# ATRACK_KEY_V1.net
KiCad netlist of a schematic drawn in Altium Designer
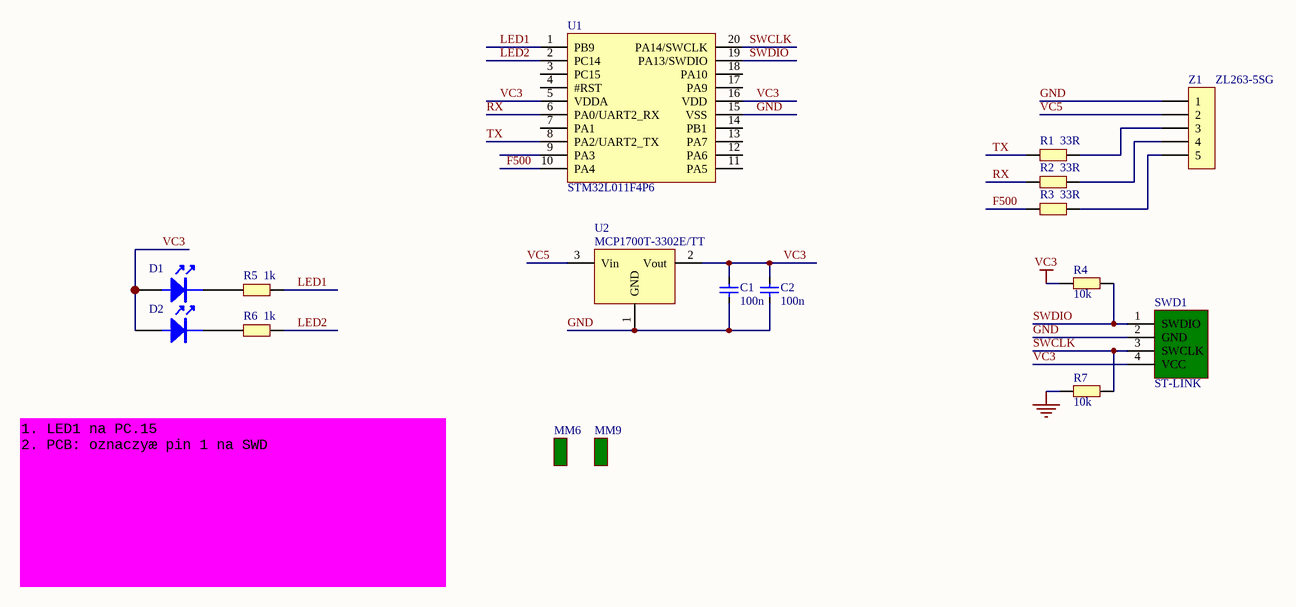
[diagram p0: ATRACK_KEY_V1.SchDoc]

(export (version "E")
  (design (tool "Eeschema 10.0.6"))
  (components
    (comp (ref "C1") (value "100n") (footprint "0603C") (libsource (lib "*") (part "CAP")))
    (comp (ref "C2") (value "100n") (footprint "0603C") (libsource (lib "*") (part "CAP")))
    (comp (ref "D1") (value "~") (footprint "0603LG") (libsource (lib "*") (part "LED")))
    (comp (ref "D2") (value "~") (footprint "0603LR") (libsource (lib "*") (part "LED")))
    (comp (ref "MM6") (value "~") (footprint "REF_CIR") (libsource (lib "*") (part "MECH")))
    (comp (ref "MM9") (value "~") (footprint "REF_SQR") (libsource (lib "*") (part "MECH")))
    (comp (ref "R1") (value "33R") (footprint "0603R") (libsource (lib "*") (part "RES3")))
    (comp (ref "R2") (value "33R") (footprint "0603R") (libsource (lib "*") (part "RES3")))
    (comp (ref "R3") (value "33R") (footprint "0603R") (libsource (lib "*") (part "RES3")))
    (comp (ref "R4") (value "10k") (footprint "0603R") (libsource (lib "*") (part "RES3")))
    (comp (ref "R5") (value "1k") (footprint "0603R") (libsource (lib "*") (part "RES3")))
    (comp (ref "R6") (value "1k") (footprint "0603R") (libsource (lib "*") (part "RES3")))
    (comp (ref "R7") (value "10k") (footprint "0603R") (libsource (lib "*") (part "RES3")))
    (comp (ref "SWD1")
      (value "ST-LINK")
      (footprint "PIN4")
      (description "Header, 4-Pin")
      (fields (field (name "PUBLISHER") "Altium Limited"))
      (libsource (lib "GkSchlib") (part "SW_CON"))
    )
    (comp (ref "U1")
      (value "STM32L011F4P6")
      (footprint "TSSOP20")
      (libsource (lib "GkSchlib") (part "STM32L011F4P6"))
    )
    (comp (ref "U2")
      (value "MCP1700T-3302E/TT")
      (footprint "SOT-23")
      (libsource (lib "*") (part "MCP1700T-3302E/TT"))
    )
    (comp (ref "Z1")
      (value "ZL263-5SG")
      (footprint "PIN5_ZL")
      (description "Connector")
      (libsource (lib "*") (part "CON5"))
    )
  )
  (nets
    (net (code "1") (name "/F500") (class "Default")
      (node (ref "R3") (pin "1") (pintype "passive"))
      (node (ref "U1") (pin "10") (pinfunction "PA4_10") (pintype "passive"))
    )
    (net (code "2") (name "/LED1") (class "Default")
      (node (ref "R5") (pin "2") (pintype "passive"))
      (node (ref "U1") (pin "1") (pinfunction "PB9_1") (pintype "passive"))
    )
    (net (code "3") (name "/LED2") (class "Default")
      (node (ref "R6") (pin "2") (pintype "passive"))
      (node (ref "U1") (pin "2") (pinfunction "PC14_2") (pintype "passive"))
    )
    (net (code "4") (name "/RX") (class "Default")
      (node (ref "R2") (pin "1") (pintype "passive"))
      (node (ref "U1") (pin "6") (pinfunction "PA0/UART2_RX_6") (pintype "passive"))
    )
    (net (code "5") (name "/SWCLK") (class "Default")
      (node (ref "R7") (pin "2") (pintype "passive"))
      (node (ref "SWD1") (pin "3") (pinfunction "SWCLK_3") (pintype "passive"))
      (node (ref "U1") (pin "20") (pinfunction "PA14/SWCLK_20") (pintype "passive"))
    )
    (net (code "6") (name "/SWDIO") (class "Default")
      (node (ref "R4") (pin "2") (pintype "passive"))
      (node (ref "SWD1") (pin "1") (pinfunction "SWDIO_1") (pintype "passive"))
      (node (ref "U1") (pin "19") (pinfunction "PA13/SWDIO_19") (pintype "passive"))
    )
    (net (code "7") (name "/TX") (class "Default")
      (node (ref "R1") (pin "1") (pintype "passive"))
      (node (ref "U1") (pin "8") (pinfunction "PA2/UART2_TX_8") (pintype "passive"))
    )
    (net (code "8") (name "/VC5") (class "Default")
      (node (ref "U2") (pin "3") (pinfunction "Vin_3") (pintype "passive"))
      (node (ref "Z1") (pin "2") (pinfunction "2_2") (pintype "passive"))
    )
    (net (code "9") (name "GND") (class "Default")
      (node (ref "C1") (pin "2") (pintype "passive"))
      (node (ref "C2") (pin "2") (pintype "passive"))
      (node (ref "R7") (pin "1") (pintype "passive"))
      (node (ref "SWD1") (pin "2") (pinfunction "GND_2") (pintype "passive"))
      (node (ref "U1") (pin "15") (pinfunction "VSS_15") (pintype "passive"))
      (node (ref "U2") (pin "1") (pinfunction "GND_1") (pintype "passive"))
      (node (ref "Z1") (pin "1") (pinfunction "1_1") (pintype "passive"))
    )
    (net (code "10") (name "Net-(D1-2)") (class "Default")
      (node (ref "D1") (pin "K") (pinfunction "2_K") (pintype "passive"))
      (node (ref "R5") (pin "1") (pintype "passive"))
    )
    (net (code "11") (name "Net-(D2-2)") (class "Default")
      (node (ref "D2") (pin "K") (pinfunction "2_K") (pintype "passive"))
      (node (ref "R6") (pin "1") (pintype "passive"))
    )
    (net (code "12") (name "Net-(R1-Pad2)") (class "Default")
      (node (ref "R1") (pin "2") (pintype "passive"))
      (node (ref "Z1") (pin "3") (pinfunction "3_3") (pintype "passive"))
    )
    (net (code "13") (name "Net-(R2-Pad2)") (class "Default")
      (node (ref "R2") (pin "2") (pintype "passive"))
      (node (ref "Z1") (pin "4") (pinfunction "4_4") (pintype "passive"))
    )
    (net (code "14") (name "Net-(R3-Pad2)") (class "Default")
      (node (ref "R3") (pin "2") (pintype "passive"))
      (node (ref "Z1") (pin "5") (pinfunction "5_5") (pintype "passive"))
    )
    (net (code "15") (name "VC3") (class "Default")
      (node (ref "C1") (pin "1") (pintype "passive"))
      (node (ref "C2") (pin "1") (pintype "passive"))
      (node (ref "D1") (pin "A") (pinfunction "1_A") (pintype "passive"))
      (node (ref "D2") (pin "A") (pinfunction "1_A") (pintype "passive"))
      (node (ref "R4") (pin "1") (pintype "passive"))
      (node (ref "SWD1") (pin "4") (pinfunction "VCC_4") (pintype "passive"))
      (node (ref "U1") (pin "16") (pinfunction "VDD_16") (pintype "passive"))
      (node (ref "U1") (pin "5") (pinfunction "VDDA_5") (pintype "passive"))
      (node (ref "U2") (pin "2") (pinfunction "Vout_2") (pintype "passive"))
    )
    (net (code "16") (name "unconnected-(U1-#RST-Pad4)") (class "Default")
      (node (ref "U1") (pin "4") (pinfunction "#RST_4") (pintype "passive"))
    )
    (net (code "17") (name "unconnected-(U1-PA1-Pad7)") (class "Default")
      (node (ref "U1") (pin "7") (pinfunction "PA1_7") (pintype "passive"))
    )
    (net (code "18") (name "unconnected-(U1-PA3-Pad9)") (class "Default")
      (node (ref "U1") (pin "9") (pinfunction "PA3_9") (pintype "passive"))
    )
    (net (code "19") (name "unconnected-(U1-PA5-Pad11)") (class "Default")
      (node (ref "U1") (pin "11") (pinfunction "PA5_11") (pintype "passive"))
    )
    (net (code "20") (name "unconnected-(U1-PA6-Pad12)") (class "Default")
      (node (ref "U1") (pin "12") (pinfunction "PA6_12") (pintype "passive"))
    )
    (net (code "21") (name "unconnected-(U1-PA7-Pad13)") (class "Default")
      (node (ref "U1") (pin "13") (pinfunction "PA7_13") (pintype "passive"))
    )
    (net (code "22") (name "unconnected-(U1-PA9-Pad17)") (class "Default")
      (node (ref "U1") (pin "17") (pinfunction "PA9_17") (pintype "passive"))
    )
    (net (code "23") (name "unconnected-(U1-PA10-Pad18)") (class "Default")
      (node (ref "U1") (pin "18") (pinfunction "PA10_18") (pintype "passive"))
    )
    (net (code "24") (name "unconnected-(U1-PB1-Pad14)") (class "Default")
      (node (ref "U1") (pin "14") (pinfunction "PB1_14") (pintype "passive"))
    )
    (net (code "25") (name "unconnected-(U1-PC15-Pad3)") (class "Default")
      (node (ref "U1") (pin "3") (pinfunction "PC15_3") (pintype "passive"))
    )
  )
)
